# eMMC.net
KiCad netlist of a schematic drawn in Altium Designer
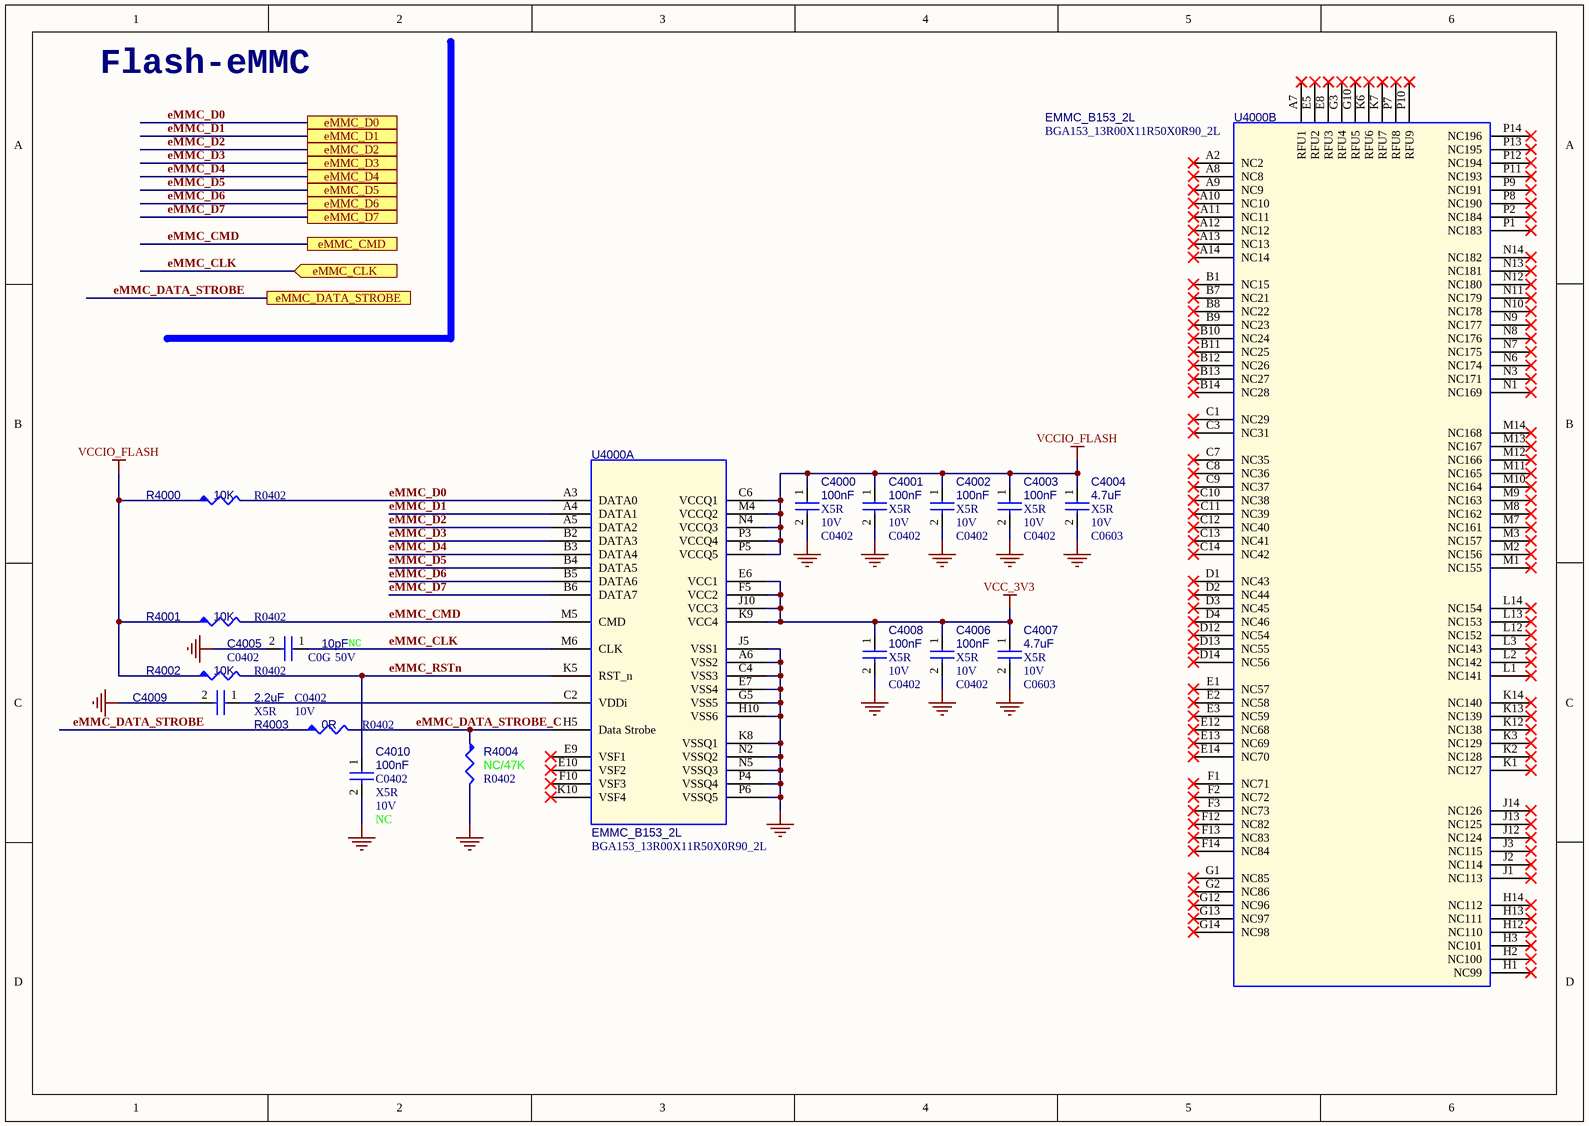
[diagram p0: eMMC.SchDoc]

(export (version "E")
  (design (tool "Eeschema 10.0.6"))
  (components
    (comp (ref "C4000")
      (value "100nF")
      (footprint "C0402")
      (description "cap,100.00nF,+/-10%,10V,X5R,C0402")
      (fields
        (field (name "DIELECTRIC") "X5R")
        (field (name "PCB FOOTPRINT") "C0402")
        (field (name "VOLTAGE") "10V")
        (field (name "MANUFACTURER") "TDK")
        (field (name "TOLERANCE") "10%")
        (field (name "CREATED BY") "JJJ")
      )
      (libsource (lib "RK3562_REF") (part "CAP NP"))
    )
    (comp (ref "C4001")
      (value "100nF")
      (footprint "C0402")
      (description "cap,100.00nF,+/-10%,10V,X5R,C0402")
      (fields
        (field (name "DIELECTRIC") "X5R")
        (field (name "PCB FOOTPRINT") "C0402")
        (field (name "VOLTAGE") "10V")
        (field (name "TOLERANCE") "10%")
        (field (name "MANUFACTURER") "TDK")
        (field (name "CREATED BY") "JJJ")
      )
      (libsource (lib "RK3562_REF") (part "CAP NP"))
    )
    (comp (ref "C4002")
      (value "100nF")
      (footprint "C0402")
      (description "cap,100.00nF,+/-10%,10V,X5R,C0402")
      (fields
        (field (name "DIELECTRIC") "X5R")
        (field (name "PCB FOOTPRINT") "C0402")
        (field (name "VOLTAGE") "10V")
        (field (name "TOLERANCE") "10%")
        (field (name "MANUFACTURER") "TDK")
        (field (name "CREATED BY") "JJJ")
      )
      (libsource (lib "RK3562_REF") (part "CAP NP"))
    )
    (comp (ref "C4003")
      (value "100nF")
      (footprint "C0402")
      (description "cap,100.00nF,+/-10%,10V,X5R,C0402")
      (fields
        (field (name "DIELECTRIC") "X5R")
        (field (name "PCB FOOTPRINT") "C0402")
        (field (name "VOLTAGE") "10V")
        (field (name "MANUFACTURER") "TDK")
        (field (name "TOLERANCE") "10%")
        (field (name "CREATED BY") "JJJ")
      )
      (libsource (lib "RK3562_REF") (part "CAP NP"))
    )
    (comp (ref "C4004")
      (value "4.7uF")
      (footprint "C0603")
      (description "cap,4.70uF,+/-10%,10V,X5R,C0603")
      (fields
        (field (name "DIELECTRIC") "X5R")
        (field (name "PCB FOOTPRINT") "C0603")
        (field (name "VOLTAGE") "10V")
        (field (name "TOLERANCE") "10%")
        (field (name "MANUFACTURER") "TDK")
        (field (name "CREATED BY") "JJJ")
      )
      (libsource (lib "RK3562_REF") (part "CAP NP"))
    )
    (comp (ref "C4005")
      (value "10pF")
      (footprint "C0402")
      (description "cap,10.00pF,+/-0.5,50V,C0G,C0402")
      (fields
        (field (name "DIELECTRIC") "C0G")
        (field (name "PCB FOOTPRINT") "C0402")
        (field (name "VOLTAGE") "50V")
        (field (name "OPTION") "NC")
        (field (name "TOLERANCE") "+/-0.5pF")
        (field (name "MANUFACTURER") "TDK")
        (field (name "CREATED BY") "JJJ")
      )
      (libsource (lib "RK3562_REF") (part "CAP NP"))
    )
    (comp (ref "C4006")
      (value "100nF")
      (footprint "C0402")
      (description "cap,100.00nF,+/-10%,10V,X5R,C0402")
      (fields
        (field (name "DIELECTRIC") "X5R")
        (field (name "PCB FOOTPRINT") "C0402")
        (field (name "VOLTAGE") "10V")
        (field (name "MANUFACTURER") "TDK")
        (field (name "TOLERANCE") "10%")
        (field (name "CREATED BY") "JJJ")
      )
      (libsource (lib "RK3562_REF") (part "CAP NP"))
    )
    (comp (ref "C4007")
      (value "4.7uF")
      (footprint "C0603")
      (description "cap,4.70uF,+/-10%,10V,X5R,C0603")
      (fields
        (field (name "DIELECTRIC") "X5R")
        (field (name "PCB FOOTPRINT") "C0603")
        (field (name "VOLTAGE") "10V")
        (field (name "TOLERANCE") "10%")
        (field (name "MANUFACTURER") "TDK")
        (field (name "CREATED BY") "JJJ")
      )
      (libsource (lib "RK3562_REF") (part "CAP NP"))
    )
    (comp (ref "C4008")
      (value "100nF")
      (footprint "C0402")
      (description "cap,100.00nF,+/-10%,10V,X5R,C0402")
      (fields
        (field (name "DIELECTRIC") "X5R")
        (field (name "PCB FOOTPRINT") "C0402")
        (field (name "VOLTAGE") "10V")
        (field (name "MANUFACTURER") "TDK")
        (field (name "TOLERANCE") "10%")
        (field (name "CREATED BY") "JJJ")
      )
      (libsource (lib "RK3562_REF") (part "CAP NP"))
    )
    (comp (ref "C4009")
      (value "2.2uF")
      (footprint "C0402")
      (description "cap,2.20uF,+/-10%,10V,X5R,C0402")
      (fields
        (field (name "DIELECTRIC") "X5R")
        (field (name "PCB FOOTPRINT") "C0402")
        (field (name "VOLTAGE") "10V")
        (field (name "TOLERANCE") "10%")
        (field (name "MANUFACTURER") "TDK")
        (field (name "CREATED BY") "JJJ")
      )
      (libsource (lib "RK3562_REF") (part "CAP NP"))
    )
    (comp (ref "C4010")
      (value "100nF")
      (footprint "C0402")
      (description "cap,100.00nF,+/-10%,10V,X5R,C0402")
      (fields
        (field (name "DIELECTRIC") "X5R")
        (field (name "PCB FOOTPRINT") "C0402")
        (field (name "VOLTAGE") "10V")
        (field (name "MANUFACTURER") "TDK")
        (field (name "TOLERANCE") "10%")
        (field (name "OPTION") "NC")
        (field (name "CREATED BY") "JJJ")
      )
      (libsource (lib "RK3562_REF") (part "CAP NP"))
    )
    (comp (ref "R4000")
      (value "10K")
      (footprint "R0402")
      (description "通用厚膜电阻,10K,+/-5%,R0402,1/16W.")
      (fields
        (field (name "TOLERANCE") "5%")
        (field (name "PCB FOOTPRINT") "R0402")
        (field (name "MANUFACTURER") "YAGEO")
        (field (name "CREATED BY") "YTL")
      )
      (libsource (lib "RK3562_REF") (part "RESISTOR5"))
    )
    (comp (ref "R4001")
      (value "10K")
      (footprint "R0402")
      (description "通用厚膜电阻,10K,+/-5%,R0402,1/16W.")
      (fields
        (field (name "TOLERANCE") "5%")
        (field (name "PCB FOOTPRINT") "R0402")
        (field (name "MANUFACTURER") "YAGEO")
        (field (name "CREATED BY") "YTL")
      )
      (libsource (lib "RK3562_REF") (part "RESISTOR5"))
    )
    (comp (ref "R4002")
      (value "10K")
      (footprint "R0402")
      (description "通用厚膜电阻,10K,+/-5%,R0402,1/16W.")
      (fields
        (field (name "TOLERANCE") "5%")
        (field (name "PCB FOOTPRINT") "R0402")
        (field (name "MANUFACTURER") "YAGEO")
        (field (name "CREATED BY") "YTL")
      )
      (libsource (lib "RK3562_REF") (part "RESISTOR5"))
    )
    (comp (ref "R4003")
      (value "0R")
      (footprint "R0402")
      (description "通用厚膜电阻,0R,+/-5%,R0402,1/16W.")
      (fields
        (field (name "TOLERANCE") "5%")
        (field (name "PCB FOOTPRINT") "R0402")
        (field (name "MANUFACTURER") "YAGEO")
        (field (name "CREATED BY") "YTL")
      )
      (libsource (lib "RK3562_REF") (part "RESISTOR5"))
    )
    (comp (ref "R4004")
      (value "NC/47K")
      (footprint "R0402")
      (description "通用厚膜电阻,47K,+/-5%,R0402,1/16W.")
      (fields
        (field (name "PCB FOOTPRINT") "R0402")
        (field (name "TOLERANCE") "5%")
        (field (name "MANUFACTURER") "YAGEO")
        (field (name "CREATED BY") "YTL")
      )
      (libsource (lib "RK3562_REF") (part "RESISTOR5_NC"))
    )
    (comp (ref "U4000")
      (value "EMMC_B153_2L")
      (footprint "FBGA-153_L13.0-W11.5-P0.50_KLMAG1JETD-B041")
      (description "EMMC_B153_2L,更好的满足工艺需求，Fanout方式部分走线跨接再球位上，挖除A1\\C5球位")
      (fields (field (name "PCB FOOTPRINT") "BGA153_13R00X11R50X0R90_2L") (field (name "CREATED BY") "YWQ"))
      (libsource (lib "RK3562_REF") (part "INAND_EMMC_153_2L"))
    )
  )
  (nets
    (net (code "1") (name "/eMMC_CLK") (class "Default")
      (node (ref "C4005") (pin "1") (pinfunction "1_1") (pintype "passive"))
      (node (ref "U4000") (pin "M6") (pinfunction "CLK_M6") (pintype "passive"))
    )
    (net (code "2") (name "/eMMC_CMD") (class "Default")
      (node (ref "R4001") (pin "2") (pinfunction "2_2") (pintype "passive"))
      (node (ref "U4000") (pin "M5") (pinfunction "CMD_M5") (pintype "passive"))
    )
    (net (code "3") (name "/eMMC_D0") (class "Default")
      (node (ref "R4000") (pin "2") (pinfunction "2_2") (pintype "passive"))
      (node (ref "U4000") (pin "A3") (pinfunction "DATA0_A3") (pintype "passive"))
    )
    (net (code "4") (name "/eMMC_D1") (class "Default")
      (node (ref "U4000") (pin "A4") (pinfunction "DATA1_A4") (pintype "passive"))
    )
    (net (code "5") (name "/eMMC_D2") (class "Default")
      (node (ref "U4000") (pin "A5") (pinfunction "DATA2_A5") (pintype "passive"))
    )
    (net (code "6") (name "/eMMC_D3") (class "Default")
      (node (ref "U4000") (pin "B2") (pinfunction "DATA3_B2") (pintype "passive"))
    )
    (net (code "7") (name "/eMMC_D4") (class "Default")
      (node (ref "U4000") (pin "B3") (pinfunction "DATA4_B3") (pintype "passive"))
    )
    (net (code "8") (name "/eMMC_D5") (class "Default")
      (node (ref "U4000") (pin "B4") (pinfunction "DATA5_B4") (pintype "passive"))
    )
    (net (code "9") (name "/eMMC_D6") (class "Default")
      (node (ref "U4000") (pin "B5") (pinfunction "DATA6_B5") (pintype "passive"))
    )
    (net (code "10") (name "/eMMC_D7") (class "Default")
      (node (ref "U4000") (pin "B6") (pinfunction "DATA7_B6") (pintype "passive"))
    )
    (net (code "11") (name "/eMMC_DATA_STROBE") (class "Default")
      (node (ref "R4003") (pin "1") (pinfunction "1_1") (pintype "passive"))
    )
    (net (code "12") (name "/eMMC_DATA_STROBE_C") (class "Default")
      (node (ref "R4003") (pin "2") (pinfunction "2_2") (pintype "passive"))
      (node (ref "R4004") (pin "1") (pinfunction "1_1") (pintype "passive"))
      (node (ref "U4000") (pin "H5") (pinfunction "Data_Strobe_H5") (pintype "passive"))
    )
    (net (code "13") (name "/eMMC_RSTn") (class "Default")
      (node (ref "C4010") (pin "1") (pinfunction "1_1") (pintype "passive"))
      (node (ref "R4002") (pin "2") (pinfunction "2_2") (pintype "passive"))
      (node (ref "U4000") (pin "K5") (pinfunction "RST_n_K5") (pintype "passive"))
    )
    (net (code "14") (name "GND") (class "Default")
      (node (ref "C4000") (pin "2") (pinfunction "2_2") (pintype "passive"))
      (node (ref "C4001") (pin "2") (pinfunction "2_2") (pintype "passive"))
      (node (ref "C4002") (pin "2") (pinfunction "2_2") (pintype "passive"))
      (node (ref "C4003") (pin "2") (pinfunction "2_2") (pintype "passive"))
      (node (ref "C4004") (pin "2") (pinfunction "2_2") (pintype "passive"))
      (node (ref "C4005") (pin "2") (pinfunction "2_2") (pintype "passive"))
      (node (ref "C4006") (pin "2") (pinfunction "2_2") (pintype "passive"))
      (node (ref "C4007") (pin "2") (pinfunction "2_2") (pintype "passive"))
      (node (ref "C4008") (pin "2") (pinfunction "2_2") (pintype "passive"))
      (node (ref "C4009") (pin "2") (pinfunction "2_2") (pintype "passive"))
      (node (ref "C4010") (pin "2") (pinfunction "2_2") (pintype "passive"))
      (node (ref "R4004") (pin "2") (pinfunction "2_2") (pintype "passive"))
      (node (ref "U4000") (pin "A6") (pinfunction "VSS2_A6") (pintype "passive"))
      (node (ref "U4000") (pin "C4") (pinfunction "VSS3_C4") (pintype "passive"))
      (node (ref "U4000") (pin "E7") (pinfunction "VSS4_E7") (pintype "passive"))
      (node (ref "U4000") (pin "G5") (pinfunction "VSS5_G5") (pintype "passive"))
      (node (ref "U4000") (pin "H10") (pinfunction "VSS6_H10") (pintype "passive"))
      (node (ref "U4000") (pin "J5") (pinfunction "VSS1_J5") (pintype "passive"))
      (node (ref "U4000") (pin "K8") (pinfunction "VSSQ1_K8") (pintype "passive"))
      (node (ref "U4000") (pin "N2") (pinfunction "VSSQ2_N2") (pintype "passive"))
      (node (ref "U4000") (pin "N5") (pinfunction "VSSQ3_N5") (pintype "passive"))
      (node (ref "U4000") (pin "P4") (pinfunction "VSSQ4_P4") (pintype "passive"))
      (node (ref "U4000") (pin "P6") (pinfunction "VSSQ5_P6") (pintype "passive"))
    )
    (net (code "15") (name "Net-(U4000A-VDDi)") (class "Default")
      (node (ref "C4009") (pin "1") (pinfunction "1_1") (pintype "passive"))
      (node (ref "U4000") (pin "C2") (pinfunction "VDDi_C2") (pintype "passive"))
    )
    (net (code "16") (name "VCCIO_FLASH") (class "Default")
      (node (ref "C4000") (pin "1") (pinfunction "1_1") (pintype "passive"))
      (node (ref "C4001") (pin "1") (pinfunction "1_1") (pintype "passive"))
      (node (ref "C4002") (pin "1") (pinfunction "1_1") (pintype "passive"))
      (node (ref "C4003") (pin "1") (pinfunction "1_1") (pintype "passive"))
      (node (ref "C4004") (pin "1") (pinfunction "1_1") (pintype "passive"))
      (node (ref "R4000") (pin "1") (pinfunction "1_1") (pintype "passive"))
      (node (ref "R4001") (pin "1") (pinfunction "1_1") (pintype "passive"))
      (node (ref "R4002") (pin "1") (pinfunction "1_1") (pintype "passive"))
      (node (ref "U4000") (pin "C6") (pinfunction "VCCQ1_C6") (pintype "passive"))
      (node (ref "U4000") (pin "M4") (pinfunction "VCCQ2_M4") (pintype "passive"))
      (node (ref "U4000") (pin "N4") (pinfunction "VCCQ3_N4") (pintype "passive"))
      (node (ref "U4000") (pin "P3") (pinfunction "VCCQ4_P3") (pintype "passive"))
      (node (ref "U4000") (pin "P5") (pinfunction "VCCQ5_P5") (pintype "passive"))
    )
    (net (code "17") (name "VCC_3V3") (class "Default")
      (node (ref "C4006") (pin "1") (pinfunction "1_1") (pintype "passive"))
      (node (ref "C4007") (pin "1") (pinfunction "1_1") (pintype "passive"))
      (node (ref "C4008") (pin "1") (pinfunction "1_1") (pintype "passive"))
      (node (ref "U4000") (pin "E6") (pinfunction "VCC1_E6") (pintype "passive"))
      (node (ref "U4000") (pin "F5") (pinfunction "VCC2_F5") (pintype "passive"))
      (node (ref "U4000") (pin "J10") (pinfunction "VCC3_J10") (pintype "passive"))
      (node (ref "U4000") (pin "K9") (pinfunction "VCC4_K9") (pintype "passive"))
    )
    (net (code "18") (name "unconnected-(U4000A-VSF1-PadE9)") (class "Default")
      (node (ref "U4000") (pin "E9") (pinfunction "VSF1_E9") (pintype "passive+no_connect"))
    )
    (net (code "19") (name "unconnected-(U4000A-VSF2-PadE10)") (class "Default")
      (node (ref "U4000") (pin "E10") (pinfunction "VSF2_E10") (pintype "passive+no_connect"))
    )
    (net (code "20") (name "unconnected-(U4000A-VSF3-PadF10)") (class "Default")
      (node (ref "U4000") (pin "F10") (pinfunction "VSF3_F10") (pintype "passive+no_connect"))
    )
    (net (code "21") (name "unconnected-(U4000A-VSF4-PadK10)") (class "Default")
      (node (ref "U4000") (pin "K10") (pinfunction "VSF4_K10") (pintype "passive+no_connect"))
    )
    (net (code "22") (name "unconnected-(U4000B-NC2-PadA2)") (class "Default")
      (node (ref "U4000") (pin "A2") (pinfunction "NC2_A2") (pintype "passive+no_connect"))
    )
    (net (code "23") (name "unconnected-(U4000B-NC8-PadA8)") (class "Default")
      (node (ref "U4000") (pin "A8") (pinfunction "NC8_A8") (pintype "passive+no_connect"))
    )
    (net (code "24") (name "unconnected-(U4000B-NC9-PadA9)") (class "Default")
      (node (ref "U4000") (pin "A9") (pinfunction "NC9_A9") (pintype "passive+no_connect"))
    )
    (net (code "25") (name "unconnected-(U4000B-NC10-PadA10)") (class "Default")
      (node (ref "U4000") (pin "A10") (pinfunction "NC10_A10") (pintype "passive+no_connect"))
    )
    (net (code "26") (name "unconnected-(U4000B-NC11-PadA11)") (class "Default")
      (node (ref "U4000") (pin "A11") (pinfunction "NC11_A11") (pintype "passive+no_connect"))
    )
    (net (code "27") (name "unconnected-(U4000B-NC12-PadA12)") (class "Default")
      (node (ref "U4000") (pin "A12") (pinfunction "NC12_A12") (pintype "passive+no_connect"))
    )
    (net (code "28") (name "unconnected-(U4000B-NC13-PadA13)") (class "Default")
      (node (ref "U4000") (pin "A13") (pinfunction "NC13_A13") (pintype "passive+no_connect"))
    )
    (net (code "29") (name "unconnected-(U4000B-NC14-PadA14)") (class "Default")
      (node (ref "U4000") (pin "A14") (pinfunction "NC14_A14") (pintype "passive+no_connect"))
    )
    (net (code "30") (name "unconnected-(U4000B-NC15-PadB1)") (class "Default")
      (node (ref "U4000") (pin "B1") (pinfunction "NC15_B1") (pintype "passive+no_connect"))
    )
    (net (code "31") (name "unconnected-(U4000B-NC21-PadB7)") (class "Default")
      (node (ref "U4000") (pin "B7") (pinfunction "NC21_B7") (pintype "passive+no_connect"))
    )
    (net (code "32") (name "unconnected-(U4000B-NC22-PadB8)") (class "Default")
      (node (ref "U4000") (pin "B8") (pinfunction "NC22_B8") (pintype "passive+no_connect"))
    )
    (net (code "33") (name "unconnected-(U4000B-NC23-PadB9)") (class "Default")
      (node (ref "U4000") (pin "B9") (pinfunction "NC23_B9") (pintype "passive+no_connect"))
    )
    (net (code "34") (name "unconnected-(U4000B-NC24-PadB10)") (class "Default")
      (node (ref "U4000") (pin "B10") (pinfunction "NC24_B10") (pintype "passive+no_connect"))
    )
    (net (code "35") (name "unconnected-(U4000B-NC25-PadB11)") (class "Default")
      (node (ref "U4000") (pin "B11") (pinfunction "NC25_B11") (pintype "passive+no_connect"))
    )
    (net (code "36") (name "unconnected-(U4000B-NC26-PadB12)") (class "Default")
      (node (ref "U4000") (pin "B12") (pinfunction "NC26_B12") (pintype "passive+no_connect"))
    )
    (net (code "37") (name "unconnected-(U4000B-NC27-PadB13)") (class "Default")
      (node (ref "U4000") (pin "B13") (pinfunction "NC27_B13") (pintype "passive+no_connect"))
    )
    (net (code "38") (name "unconnected-(U4000B-NC28-PadB14)") (class "Default")
      (node (ref "U4000") (pin "B14") (pinfunction "NC28_B14") (pintype "passive+no_connect"))
    )
    (net (code "39") (name "unconnected-(U4000B-NC29-PadC1)") (class "Default")
      (node (ref "U4000") (pin "C1") (pinfunction "NC29_C1") (pintype "passive+no_connect"))
    )
    (net (code "40") (name "unconnected-(U4000B-NC31-PadC3)") (class "Default")
      (node (ref "U4000") (pin "C3") (pinfunction "NC31_C3") (pintype "passive+no_connect"))
    )
    (net (code "41") (name "unconnected-(U4000B-NC35-PadC7)") (class "Default")
      (node (ref "U4000") (pin "C7") (pinfunction "NC35_C7") (pintype "passive+no_connect"))
    )
    (net (code "42") (name "unconnected-(U4000B-NC36-PadC8)") (class "Default")
      (node (ref "U4000") (pin "C8") (pinfunction "NC36_C8") (pintype "passive+no_connect"))
    )
    (net (code "43") (name "unconnected-(U4000B-NC37-PadC9)") (class "Default")
      (node (ref "U4000") (pin "C9") (pinfunction "NC37_C9") (pintype "passive+no_connect"))
    )
    (net (code "44") (name "unconnected-(U4000B-NC38-PadC10)") (class "Default")
      (node (ref "U4000") (pin "C10") (pinfunction "NC38_C10") (pintype "passive+no_connect"))
    )
    (net (code "45") (name "unconnected-(U4000B-NC39-PadC11)") (class "Default")
      (node (ref "U4000") (pin "C11") (pinfunction "NC39_C11") (pintype "passive+no_connect"))
    )
    (net (code "46") (name "unconnected-(U4000B-NC40-PadC12)") (class "Default")
      (node (ref "U4000") (pin "C12") (pinfunction "NC40_C12") (pintype "passive+no_connect"))
    )
    (net (code "47") (name "unconnected-(U4000B-NC41-PadC13)") (class "Default")
      (node (ref "U4000") (pin "C13") (pinfunction "NC41_C13") (pintype "passive+no_connect"))
    )
    (net (code "48") (name "unconnected-(U4000B-NC42-PadC14)") (class "Default")
      (node (ref "U4000") (pin "C14") (pinfunction "NC42_C14") (pintype "passive+no_connect"))
    )
    (net (code "49") (name "unconnected-(U4000B-NC43-PadD1)") (class "Default")
      (node (ref "U4000") (pin "D1") (pinfunction "NC43_D1") (pintype "passive+no_connect"))
    )
    (net (code "50") (name "unconnected-(U4000B-NC44-PadD2)") (class "Default")
      (node (ref "U4000") (pin "D2") (pinfunction "NC44_D2") (pintype "passive+no_connect"))
    )
    (net (code "51") (name "unconnected-(U4000B-NC45-PadD3)") (class "Default")
      (node (ref "U4000") (pin "D3") (pinfunction "NC45_D3") (pintype "passive+no_connect"))
    )
    (net (code "52") (name "unconnected-(U4000B-NC46-PadD4)") (class "Default")
      (node (ref "U4000") (pin "D4") (pinfunction "NC46_D4") (pintype "passive+no_connect"))
    )
    (net (code "53") (name "unconnected-(U4000B-NC54-PadD12)") (class "Default")
      (node (ref "U4000") (pin "D12") (pinfunction "NC54_D12") (pintype "passive+no_connect"))
    )
    (net (code "54") (name "unconnected-(U4000B-NC55-PadD13)") (class "Default")
      (node (ref "U4000") (pin "D13") (pinfunction "NC55_D13") (pintype "passive+no_connect"))
    )
    (net (code "55") (name "unconnected-(U4000B-NC56-PadD14)") (class "Default")
      (node (ref "U4000") (pin "D14") (pinfunction "NC56_D14") (pintype "passive+no_connect"))
    )
    (net (code "56") (name "unconnected-(U4000B-NC57-PadE1)") (class "Default")
      (node (ref "U4000") (pin "E1") (pinfunction "NC57_E1") (pintype "passive+no_connect"))
    )
    (net (code "57") (name "unconnected-(U4000B-NC58-PadE2)") (class "Default")
      (node (ref "U4000") (pin "E2") (pinfunction "NC58_E2") (pintype "passive+no_connect"))
    )
    (net (code "58") (name "unconnected-(U4000B-NC59-PadE3)") (class "Default")
      (node (ref "U4000") (pin "E3") (pinfunction "NC59_E3") (pintype "passive+no_connect"))
    )
    (net (code "59") (name "unconnected-(U4000B-NC68-PadE12)") (class "Default")
      (node (ref "U4000") (pin "E12") (pinfunction "NC68_E12") (pintype "passive+no_connect"))
    )
    (net (code "60") (name "unconnected-(U4000B-NC69-PadE13)") (class "Default")
      (node (ref "U4000") (pin "E13") (pinfunction "NC69_E13") (pintype "passive+no_connect"))
    )
    (net (code "61") (name "unconnected-(U4000B-NC70-PadE14)") (class "Default")
      (node (ref "U4000") (pin "E14") (pinfunction "NC70_E14") (pintype "passive+no_connect"))
    )
    (net (code "62") (name "unconnected-(U4000B-NC71-PadF1)") (class "Default")
      (node (ref "U4000") (pin "F1") (pinfunction "NC71_F1") (pintype "passive+no_connect"))
    )
    (net (code "63") (name "unconnected-(U4000B-NC72-PadF2)") (class "Default")
      (node (ref "U4000") (pin "F2") (pinfunction "NC72_F2") (pintype "passive+no_connect"))
    )
    (net (code "64") (name "unconnected-(U4000B-NC73-PadF3)") (class "Default")
      (node (ref "U4000") (pin "F3") (pinfunction "NC73_F3") (pintype "passive+no_connect"))
    )
    (net (code "65") (name "unconnected-(U4000B-NC82-PadF12)") (class "Default")
      (node (ref "U4000") (pin "F12") (pinfunction "NC82_F12") (pintype "passive+no_connect"))
    )
    (net (code "66") (name "unconnected-(U4000B-NC83-PadF13)") (class "Default")
      (node (ref "U4000") (pin "F13") (pinfunction "NC83_F13") (pintype "passive+no_connect"))
    )
    (net (code "67") (name "unconnected-(U4000B-NC84-PadF14)") (class "Default")
      (node (ref "U4000") (pin "F14") (pinfunction "NC84_F14") (pintype "passive+no_connect"))
    )
    (net (code "68") (name "unconnected-(U4000B-NC85-PadG1)") (class "Default")
      (node (ref "U4000") (pin "G1") (pinfunction "NC85_G1") (pintype "passive+no_connect"))
    )
    (net (code "69") (name "unconnected-(U4000B-NC86-PadG2)") (class "Default")
      (node (ref "U4000") (pin "G2") (pinfunction "NC86_G2") (pintype "passive+no_connect"))
    )
    (net (code "70") (name "unconnected-(U4000B-NC96-PadG12)") (class "Default")
      (node (ref "U4000") (pin "G12") (pinfunction "NC96_G12") (pintype "passive+no_connect"))
    )
    (net (code "71") (name "unconnected-(U4000B-NC97-PadG13)") (class "Default")
      (node (ref "U4000") (pin "G13") (pinfunction "NC97_G13") (pintype "passive+no_connect"))
    )
    (net (code "72") (name "unconnected-(U4000B-NC98-PadG14)") (class "Default")
      (node (ref "U4000") (pin "G14") (pinfunction "NC98_G14") (pintype "passive+no_connect"))
    )
    (net (code "73") (name "unconnected-(U4000B-NC99-PadH1)") (class "Default")
      (node (ref "U4000") (pin "H1") (pinfunction "NC99_H1") (pintype "passive+no_connect"))
    )
    (net (code "74") (name "unconnected-(U4000B-NC100-PadH2)") (class "Default")
      (node (ref "U4000") (pin "H2") (pinfunction "NC100_H2") (pintype "passive+no_connect"))
    )
    (net (code "75") (name "unconnected-(U4000B-NC101-PadH3)") (class "Default")
      (node (ref "U4000") (pin "H3") (pinfunction "NC101_H3") (pintype "passive+no_connect"))
    )
    (net (code "76") (name "unconnected-(U4000B-NC110-PadH12)") (class "Default")
      (node (ref "U4000") (pin "H12") (pinfunction "NC110_H12") (pintype "passive+no_connect"))
    )
    (net (code "77") (name "unconnected-(U4000B-NC111-PadH13)") (class "Default")
      (node (ref "U4000") (pin "H13") (pinfunction "NC111_H13") (pintype "passive+no_connect"))
    )
    (net (code "78") (name "unconnected-(U4000B-NC112-PadH14)") (class "Default")
      (node (ref "U4000") (pin "H14") (pinfunction "NC112_H14") (pintype "passive+no_connect"))
    )
    (net (code "79") (name "unconnected-(U4000B-NC113-PadJ1)") (class "Default")
      (node (ref "U4000") (pin "J1") (pinfunction "NC113_J1") (pintype "passive+no_connect"))
    )
    (net (code "80") (name "unconnected-(U4000B-NC114-PadJ2)") (class "Default")
      (node (ref "U4000") (pin "J2") (pinfunction "NC114_J2") (pintype "passive+no_connect"))
    )
    (net (code "81") (name "unconnected-(U4000B-NC115-PadJ3)") (class "Default")
      (node (ref "U4000") (pin "J3") (pinfunction "NC115_J3") (pintype "passive+no_connect"))
    )
    (net (code "82") (name "unconnected-(U4000B-NC124-PadJ12)") (class "Default")
      (node (ref "U4000") (pin "J12") (pinfunction "NC124_J12") (pintype "passive+no_connect"))
    )
    (net (code "83") (name "unconnected-(U4000B-NC125-PadJ13)") (class "Default")
      (node (ref "U4000") (pin "J13") (pinfunction "NC125_J13") (pintype "passive+no_connect"))
    )
    (net (code "84") (name "unconnected-(U4000B-NC126-PadJ14)") (class "Default")
      (node (ref "U4000") (pin "J14") (pinfunction "NC126_J14") (pintype "passive+no_connect"))
    )
    (net (code "85") (name "unconnected-(U4000B-NC127-PadK1)") (class "Default")
      (node (ref "U4000") (pin "K1") (pinfunction "NC127_K1") (pintype "passive+no_connect"))
    )
    (net (code "86") (name "unconnected-(U4000B-NC128-PadK2)") (class "Default")
      (node (ref "U4000") (pin "K2") (pinfunction "NC128_K2") (pintype "passive+no_connect"))
    )
    (net (code "87") (name "unconnected-(U4000B-NC129-PadK3)") (class "Default")
      (node (ref "U4000") (pin "K3") (pinfunction "NC129_K3") (pintype "passive+no_connect"))
    )
    (net (code "88") (name "unconnected-(U4000B-NC138-PadK12)") (class "Default")
      (node (ref "U4000") (pin "K12") (pinfunction "NC138_K12") (pintype "passive+no_connect"))
    )
    (net (code "89") (name "unconnected-(U4000B-NC139-PadK13)") (class "Default")
      (node (ref "U4000") (pin "K13") (pinfunction "NC139_K13") (pintype "passive+no_connect"))
    )
    (net (code "90") (name "unconnected-(U4000B-NC140-PadK14)") (class "Default")
      (node (ref "U4000") (pin "K14") (pinfunction "NC140_K14") (pintype "passive+no_connect"))
    )
    (net (code "91") (name "unconnected-(U4000B-NC141-PadL1)") (class "Default")
      (node (ref "U4000") (pin "L1") (pinfunction "NC141_L1") (pintype "passive+no_connect"))
    )
    (net (code "92") (name "unconnected-(U4000B-NC142-PadL2)") (class "Default")
      (node (ref "U4000") (pin "L2") (pinfunction "NC142_L2") (pintype "passive+no_connect"))
    )
    (net (code "93") (name "unconnected-(U4000B-NC143-PadL3)") (class "Default")
      (node (ref "U4000") (pin "L3") (pinfunction "NC143_L3") (pintype "passive+no_connect"))
    )
    (net (code "94") (name "unconnected-(U4000B-NC152-PadL12)") (class "Default")
      (node (ref "U4000") (pin "L12") (pinfunction "NC152_L12") (pintype "passive+no_connect"))
    )
    (net (code "95") (name "unconnected-(U4000B-NC153-PadL13)") (class "Default")
      (node (ref "U4000") (pin "L13") (pinfunction "NC153_L13") (pintype "passive+no_connect"))
    )
    (net (code "96") (name "unconnected-(U4000B-NC154-PadL14)") (class "Default")
      (node (ref "U4000") (pin "L14") (pinfunction "NC154_L14") (pintype "passive+no_connect"))
    )
    (net (code "97") (name "unconnected-(U4000B-NC155-PadM1)") (class "Default")
      (node (ref "U4000") (pin "M1") (pinfunction "NC155_M1") (pintype "passive+no_connect"))
    )
    (net (code "98") (name "unconnected-(U4000B-NC156-PadM2)") (class "Default")
      (node (ref "U4000") (pin "M2") (pinfunction "NC156_M2") (pintype "passive+no_connect"))
    )
    (net (code "99") (name "unconnected-(U4000B-NC157-PadM3)") (class "Default")
      (node (ref "U4000") (pin "M3") (pinfunction "NC157_M3") (pintype "passive+no_connect"))
    )
    (net (code "100") (name "unconnected-(U4000B-NC161-PadM7)") (class "Default")
      (node (ref "U4000") (pin "M7") (pinfunction "NC161_M7") (pintype "passive+no_connect"))
    )
    (net (code "101") (name "unconnected-(U4000B-NC162-PadM8)") (class "Default")
      (node (ref "U4000") (pin "M8") (pinfunction "NC162_M8") (pintype "passive+no_connect"))
    )
    (net (code "102") (name "unconnected-(U4000B-NC163-PadM9)") (class "Default")
      (node (ref "U4000") (pin "M9") (pinfunction "NC163_M9") (pintype "passive+no_connect"))
    )
    (net (code "103") (name "unconnected-(U4000B-NC164-PadM10)") (class "Default")
      (node (ref "U4000") (pin "M10") (pinfunction "NC164_M10") (pintype "passive+no_connect"))
    )
    (net (code "104") (name "unconnected-(U4000B-NC165-PadM11)") (class "Default")
      (node (ref "U4000") (pin "M11") (pinfunction "NC165_M11") (pintype "passive+no_connect"))
    )
    (net (code "105") (name "unconnected-(U4000B-NC166-PadM12)") (class "Default")
      (node (ref "U4000") (pin "M12") (pinfunction "NC166_M12") (pintype "passive+no_connect"))
    )
    (net (code "106") (name "unconnected-(U4000B-NC167-PadM13)") (class "Default")
      (node (ref "U4000") (pin "M13") (pinfunction "NC167_M13") (pintype "passive+no_connect"))
    )
    (net (code "107") (name "unconnected-(U4000B-NC168-PadM14)") (class "Default")
      (node (ref "U4000") (pin "M14") (pinfunction "NC168_M14") (pintype "passive+no_connect"))
    )
    (net (code "108") (name "unconnected-(U4000B-NC169-PadN1)") (class "Default")
      (node (ref "U4000") (pin "N1") (pinfunction "NC169_N1") (pintype "passive+no_connect"))
    )
    (net (code "109") (name "unconnected-(U4000B-NC171-PadN3)") (class "Default")
      (node (ref "U4000") (pin "N3") (pinfunction "NC171_N3") (pintype "passive+no_connect"))
    )
    (net (code "110") (name "unconnected-(U4000B-NC174-PadN6)") (class "Default")
      (node (ref "U4000") (pin "N6") (pinfunction "NC174_N6") (pintype "passive+no_connect"))
    )
    (net (code "111") (name "unconnected-(U4000B-NC175-PadN7)") (class "Default")
      (node (ref "U4000") (pin "N7") (pinfunction "NC175_N7") (pintype "passive+no_connect"))
    )
    (net (code "112") (name "unconnected-(U4000B-NC176-PadN8)") (class "Default")
      (node (ref "U4000") (pin "N8") (pinfunction "NC176_N8") (pintype "passive+no_connect"))
    )
    (net (code "113") (name "unconnected-(U4000B-NC177-PadN9)") (class "Default")
      (node (ref "U4000") (pin "N9") (pinfunction "NC177_N9") (pintype "passive+no_connect"))
    )
    (net (code "114") (name "unconnected-(U4000B-NC178-PadN10)") (class "Default")
      (node (ref "U4000") (pin "N10") (pinfunction "NC178_N10") (pintype "passive+no_connect"))
    )
    (net (code "115") (name "unconnected-(U4000B-NC179-PadN11)") (class "Default")
      (node (ref "U4000") (pin "N11") (pinfunction "NC179_N11") (pintype "passive+no_connect"))
    )
    (net (code "116") (name "unconnected-(U4000B-NC180-PadN12)") (class "Default")
      (node (ref "U4000") (pin "N12") (pinfunction "NC180_N12") (pintype "passive+no_connect"))
    )
    (net (code "117") (name "unconnected-(U4000B-NC181-PadN13)") (class "Default")
      (node (ref "U4000") (pin "N13") (pinfunction "NC181_N13") (pintype "passive+no_connect"))
    )
    (net (code "118") (name "unconnected-(U4000B-NC182-PadN14)") (class "Default")
      (node (ref "U4000") (pin "N14") (pinfunction "NC182_N14") (pintype "passive+no_connect"))
    )
    (net (code "119") (name "unconnected-(U4000B-NC183-PadP1)") (class "Default")
      (node (ref "U4000") (pin "P1") (pinfunction "NC183_P1") (pintype "passive+no_connect"))
    )
    (net (code "120") (name "unconnected-(U4000B-NC184-PadP2)") (class "Default")
      (node (ref "U4000") (pin "P2") (pinfunction "NC184_P2") (pintype "passive+no_connect"))
    )
    (net (code "121") (name "unconnected-(U4000B-NC190-PadP8)") (class "Default")
      (node (ref "U4000") (pin "P8") (pinfunction "NC190_P8") (pintype "passive+no_connect"))
    )
    (net (code "122") (name "unconnected-(U4000B-NC191-PadP9)") (class "Default")
      (node (ref "U4000") (pin "P9") (pinfunction "NC191_P9") (pintype "passive+no_connect"))
    )
    (net (code "123") (name "unconnected-(U4000B-NC193-PadP11)") (class "Default")
      (node (ref "U4000") (pin "P11") (pinfunction "NC193_P11") (pintype "passive+no_connect"))
    )
    (net (code "124") (name "unconnected-(U4000B-NC194-PadP12)") (class "Default")
      (node (ref "U4000") (pin "P12") (pinfunction "NC194_P12") (pintype "passive+no_connect"))
    )
    (net (code "125") (name "unconnected-(U4000B-NC195-PadP13)") (class "Default")
      (node (ref "U4000") (pin "P13") (pinfunction "NC195_P13") (pintype "passive+no_connect"))
    )
    (net (code "126") (name "unconnected-(U4000B-NC196-PadP14)") (class "Default")
      (node (ref "U4000") (pin "P14") (pinfunction "NC196_P14") (pintype "passive+no_connect"))
    )
    (net (code "127") (name "unconnected-(U4000B-RFU1-PadA7)") (class "Default")
      (node (ref "U4000") (pin "A7") (pinfunction "RFU1_A7") (pintype "passive+no_connect"))
    )
    (net (code "128") (name "unconnected-(U4000B-RFU2-PadE5)") (class "Default")
      (node (ref "U4000") (pin "E5") (pinfunction "RFU2_E5") (pintype "passive+no_connect"))
    )
    (net (code "129") (name "unconnected-(U4000B-RFU3-PadE8)") (class "Default")
      (node (ref "U4000") (pin "E8") (pinfunction "RFU3_E8") (pintype "passive+no_connect"))
    )
    (net (code "130") (name "unconnected-(U4000B-RFU4-PadG3)") (class "Default")
      (node (ref "U4000") (pin "G3") (pinfunction "RFU4_G3") (pintype "passive+no_connect"))
    )
    (net (code "131") (name "unconnected-(U4000B-RFU5-PadG10)") (class "Default")
      (node (ref "U4000") (pin "G10") (pinfunction "RFU5_G10") (pintype "passive+no_connect"))
    )
    (net (code "132") (name "unconnected-(U4000B-RFU6-PadK6)") (class "Default")
      (node (ref "U4000") (pin "K6") (pinfunction "RFU6_K6") (pintype "passive+no_connect"))
    )
    (net (code "133") (name "unconnected-(U4000B-RFU7-PadK7)") (class "Default")
      (node (ref "U4000") (pin "K7") (pinfunction "RFU7_K7") (pintype "passive+no_connect"))
    )
    (net (code "134") (name "unconnected-(U4000B-RFU8-PadP7)") (class "Default")
      (node (ref "U4000") (pin "P7") (pinfunction "RFU8_P7") (pintype "passive+no_connect"))
    )
    (net (code "135") (name "unconnected-(U4000B-RFU9-PadP10)") (class "Default")
      (node (ref "U4000") (pin "P10") (pinfunction "RFU9_P10") (pintype "passive+no_connect"))
    )
  )
)
